# RTC_Board.net
KiCad netlist of a schematic drawn in EAGLE
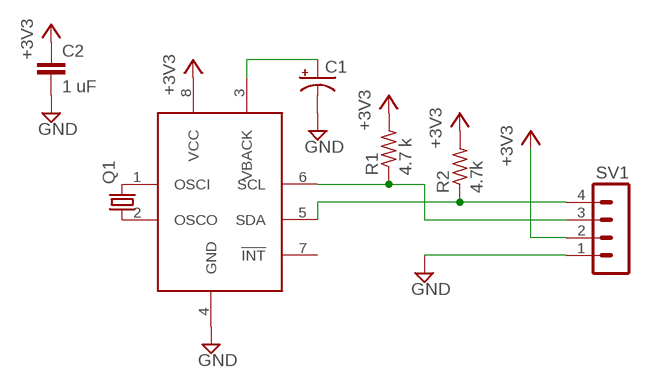
[diagram p0: schematic, sheet 1]

(export (version "E")
  (design (tool "Eeschema 10.0.6"))
  (components
    (comp (ref "C1")
      (value "CPOL-US150CLZ-1010")
      (footprint "eagle-import:150CLZ-1010")
      (libsource (lib "eagle-import") (part "CPOL-US150CLZ-1010"))
    )
    (comp (ref "C2")
      (value "1 uF")
      (footprint "eagle-import:C1206")
      (libsource (lib "eagle-import") (part "C-EUC1206"))
    )
    (comp (ref "Q1")
      (value "CRYSTALTC26H")
      (footprint "eagle-import:TC26H")
      (libsource (lib "eagle-import") (part "CRYSTALTC26H"))
    )
    (comp (ref "R1")
      (value "4.7 k")
      (footprint "eagle-import:R1206")
      (libsource (lib "eagle-import") (part "R-US_R1206"))
    )
    (comp (ref "R2")
      (value "4.7k")
      (footprint "eagle-import:R1206")
      (libsource (lib "eagle-import") (part "R-US_R1206"))
    )
    (comp (ref "SV1")
      (value "MA04-1")
      (footprint "eagle-import:MA04-1")
      (libsource (lib "eagle-import") (part "MA04-1"))
    )
    (comp (ref "U$1")
      (value "BQ32000")
      (footprint "eagle-import:SOIC8")
      (libsource (lib "eagle-import") (part "BQ32000"))
    )
  )
  (nets
    (net (code "1") (name "+3V3") (class "Default")
      (node (ref "C2") (pin "1") (pinfunction "1_1") (pintype "passive"))
      (node (ref "R1") (pin "2") (pinfunction "2_2") (pintype "passive"))
      (node (ref "R2") (pin "2") (pinfunction "2_2") (pintype "passive"))
      (node (ref "SV1") (pin "2") (pinfunction "2_2") (pintype "passive"))
      (node (ref "U$1") (pin "8") (pinfunction "VCC_8") (pintype "bidirectional"))
    )
    (net (code "2") (name "GND") (class "Default")
      (node (ref "C1") (pin "-") (pinfunction "-_-") (pintype "passive"))
      (node (ref "C2") (pin "2") (pinfunction "2_2") (pintype "passive"))
      (node (ref "SV1") (pin "1") (pinfunction "1_1") (pintype "passive"))
      (node (ref "U$1") (pin "4") (pinfunction "GND_4") (pintype "bidirectional"))
    )
    (net (code "3") (name "Net-(U$1-OSCI)") (class "Default")
      (node (ref "Q1") (pin "2") (pinfunction "2_2") (pintype "passive"))
      (node (ref "U$1") (pin "1") (pinfunction "OSCI_1") (pintype "bidirectional"))
    )
    (net (code "4") (name "Net-(U$1-OSCO)") (class "Default")
      (node (ref "Q1") (pin "1") (pinfunction "1_1") (pintype "passive"))
      (node (ref "U$1") (pin "2") (pinfunction "OSCO_2") (pintype "bidirectional"))
    )
    (net (code "5") (name "Net-(U$1-SCL)") (class "Default")
      (node (ref "R1") (pin "1") (pinfunction "1_1") (pintype "passive"))
      (node (ref "SV1") (pin "3") (pinfunction "3_3") (pintype "passive"))
      (node (ref "U$1") (pin "6") (pinfunction "SCL_6") (pintype "bidirectional"))
    )
    (net (code "6") (name "Net-(U$1-SDA)") (class "Default")
      (node (ref "R2") (pin "1") (pinfunction "1_1") (pintype "passive"))
      (node (ref "SV1") (pin "4") (pinfunction "4_4") (pintype "passive"))
      (node (ref "U$1") (pin "5") (pinfunction "SDA_5") (pintype "bidirectional"))
    )
    (net (code "7") (name "Net-(U$1-VBACK)") (class "Default")
      (node (ref "C1") (pin "+") (pinfunction "+_+") (pintype "passive"))
      (node (ref "U$1") (pin "3") (pinfunction "VBACK_3") (pintype "bidirectional"))
    )
    (net (code "8") (name "unconnected-(U$1-~{INT}-Pad7)") (class "Default")
      (node (ref "U$1") (pin "7") (pinfunction "~{INT}_7") (pintype "bidirectional"))
    )
  )
)
